# Quadcopter_v2.net
KiCad netlist of a schematic drawn in EAGLE
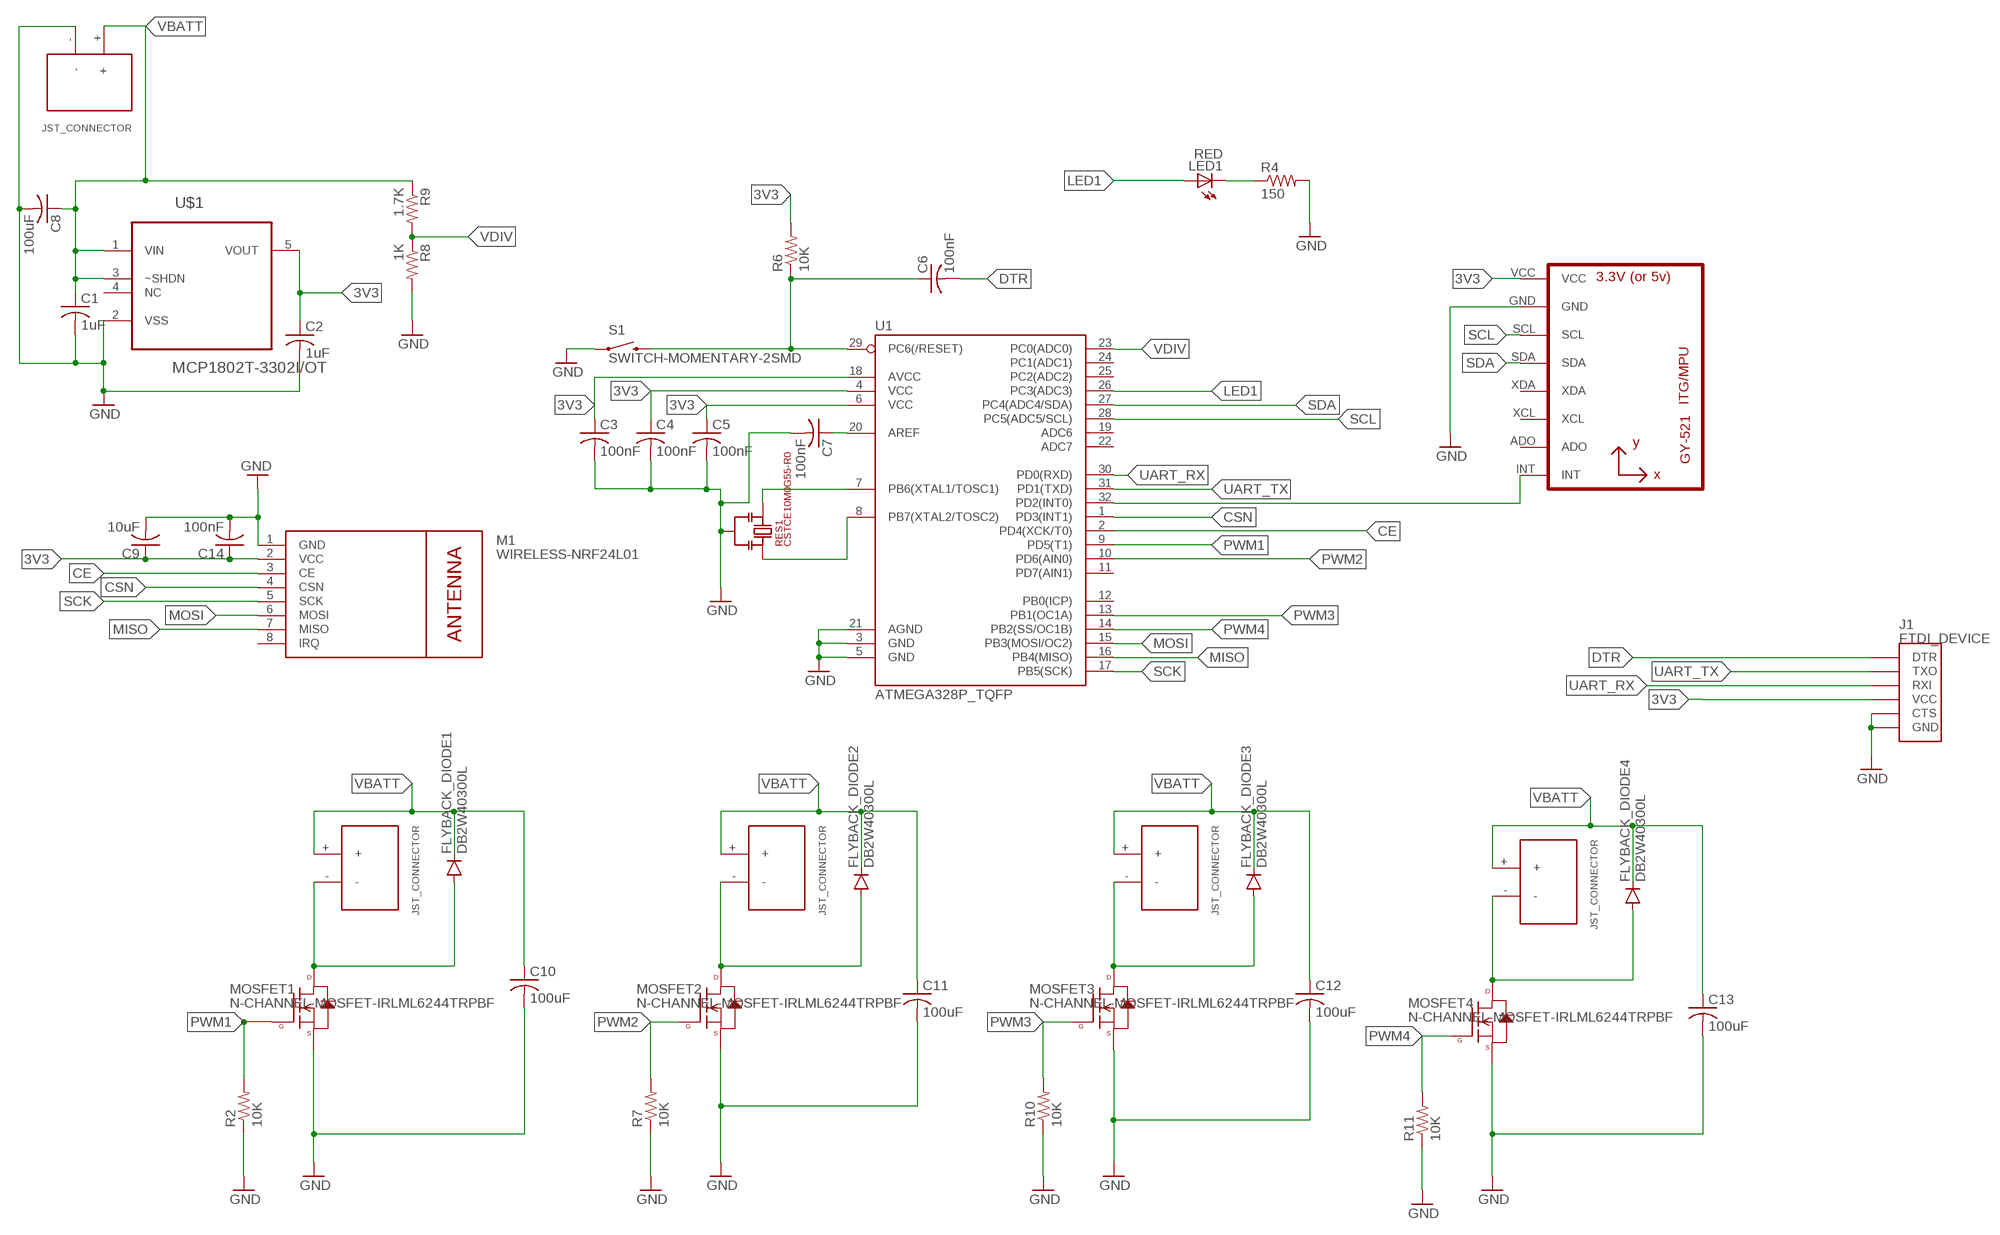
[diagram p0: schematic, sheet 1]

(export (version "E")
  (design (tool "Eeschema 10.0.6"))
  (components
    (comp (ref "C1")
      (value "1uF")
      (footprint "eagle-import:C0603")
      (libsource (lib "eagle-import") (part "C-USC0603"))
    )
    (comp (ref "C2")
      (value "1uF")
      (footprint "eagle-import:C0603")
      (libsource (lib "eagle-import") (part "C-USC0603"))
    )
    (comp (ref "C3")
      (value "100nF")
      (footprint "eagle-import:C0603")
      (libsource (lib "eagle-import") (part "C-USC0603"))
    )
    (comp (ref "C4")
      (value "100nF")
      (footprint "eagle-import:C0603")
      (libsource (lib "eagle-import") (part "C-USC0603"))
    )
    (comp (ref "C5")
      (value "100nF")
      (footprint "eagle-import:C0603")
      (libsource (lib "eagle-import") (part "C-USC0603"))
    )
    (comp (ref "C6")
      (value "100nF")
      (footprint "eagle-import:C0603")
      (libsource (lib "eagle-import") (part "C-USC0603"))
    )
    (comp (ref "C7")
      (value "100nF")
      (footprint "eagle-import:C0603")
      (libsource (lib "eagle-import") (part "C-USC0603"))
    )
    (comp (ref "C8")
      (value "100uF")
      (footprint "eagle-import:C1210")
      (libsource (lib "eagle-import") (part "C-USC1210"))
    )
    (comp (ref "C9")
      (value "10uF")
      (footprint "eagle-import:C0603")
      (libsource (lib "eagle-import") (part "C-USC0603"))
    )
    (comp (ref "C10")
      (value "100uF")
      (footprint "eagle-import:C1210")
      (libsource (lib "eagle-import") (part "C-USC1210"))
    )
    (comp (ref "C11")
      (value "100uF")
      (footprint "eagle-import:C1210")
      (libsource (lib "eagle-import") (part "C-USC1210"))
    )
    (comp (ref "C12")
      (value "100uF")
      (footprint "eagle-import:C1210")
      (libsource (lib "eagle-import") (part "C-USC1210"))
    )
    (comp (ref "C13")
      (value "100uF")
      (footprint "eagle-import:C1210")
      (libsource (lib "eagle-import") (part "C-USC1210"))
    )
    (comp (ref "C14")
      (value "100nF")
      (footprint "eagle-import:C0603")
      (libsource (lib "eagle-import") (part "C-USC0603"))
    )
    (comp (ref "FLYBACK_DIODE1")
      (value "DB2W40300L")
      (footprint "eagle-import:MINI2-F3-B")
      (libsource (lib "eagle-import") (part "DB2W40300L"))
    )
    (comp (ref "FLYBACK_DIODE2")
      (value "DB2W40300L")
      (footprint "eagle-import:MINI2-F3-B")
      (libsource (lib "eagle-import") (part "DB2W40300L"))
    )
    (comp (ref "FLYBACK_DIODE3")
      (value "DB2W40300L")
      (footprint "eagle-import:MINI2-F3-B")
      (libsource (lib "eagle-import") (part "DB2W40300L"))
    )
    (comp (ref "FLYBACK_DIODE4")
      (value "DB2W40300L")
      (footprint "eagle-import:MINI2-F3-B")
      (libsource (lib "eagle-import") (part "DB2W40300L"))
    )
    (comp (ref "J1")
      (value "FTDI_DEVICE")
      (footprint "eagle-import:FTDI_DEVICE_SIDE")
      (libsource (lib "eagle-import") (part "FTDI_DEVICE"))
    )
    (comp (ref "LED1")
      (value "RED")
      (footprint "eagle-import:CHIP-LED0603")
      (libsource (lib "eagle-import") (part "LEDCHIP-LED0603"))
    )
    (comp (ref "M1")
      (value "WIRELESS-NRF24L01")
      (footprint "eagle-import:WIRELESS-NRF24L01")
      (libsource (lib "eagle-import") (part "WIRELESS-NRF24L01"))
    )
    (comp (ref "MOSFET1")
      (value "N-CHANNEL-MOSFET-IRLML6244TRPBF")
      (footprint "eagle-import:SOT23-3")
      (libsource (lib "eagle-import") (part "N-CHANNEL-MOSFET-IRLML6244TRPBF"))
    )
    (comp (ref "MOSFET2")
      (value "N-CHANNEL-MOSFET-IRLML6244TRPBF")
      (footprint "eagle-import:SOT23-3")
      (libsource (lib "eagle-import") (part "N-CHANNEL-MOSFET-IRLML6244TRPBF"))
    )
    (comp (ref "MOSFET3")
      (value "N-CHANNEL-MOSFET-IRLML6244TRPBF")
      (footprint "eagle-import:SOT23-3")
      (libsource (lib "eagle-import") (part "N-CHANNEL-MOSFET-IRLML6244TRPBF"))
    )
    (comp (ref "MOSFET4")
      (value "N-CHANNEL-MOSFET-IRLML6244TRPBF")
      (footprint "eagle-import:SOT23-3")
      (libsource (lib "eagle-import") (part "N-CHANNEL-MOSFET-IRLML6244TRPBF"))
    )
    (comp (ref "MOTOR")
      (value "JST_CONNECTOR_FEMALE")
      (footprint "eagle-import:JST_CONNECTOR_FEMALE")
      (libsource (lib "eagle-import") (part "JST_CONNECTOR_FEMALE"))
    )
    (comp (ref "MOTOR1")
      (value "JST_CONNECTOR_FEMALE")
      (footprint "eagle-import:JST_CONNECTOR_FEMALE")
      (libsource (lib "eagle-import") (part "JST_CONNECTOR_FEMALE"))
    )
    (comp (ref "MOTOR2")
      (value "JST_CONNECTOR_FEMALE")
      (footprint "eagle-import:JST_CONNECTOR_FEMALE")
      (libsource (lib "eagle-import") (part "JST_CONNECTOR_FEMALE"))
    )
    (comp (ref "MOTOR3")
      (value "JST_CONNECTOR_FEMALE")
      (footprint "eagle-import:JST_CONNECTOR_FEMALE")
      (libsource (lib "eagle-import") (part "JST_CONNECTOR_FEMALE"))
    )
    (comp (ref "R2")
      (value "10K")
      (footprint "eagle-import:R0603")
      (libsource (lib "eagle-import") (part "R-US_R0603"))
    )
    (comp (ref "R4")
      (value "150")
      (footprint "eagle-import:R0603")
      (libsource (lib "eagle-import") (part "R-US_R0603"))
    )
    (comp (ref "R6")
      (value "10K")
      (footprint "eagle-import:R0603")
      (libsource (lib "eagle-import") (part "R-US_R0603"))
    )
    (comp (ref "R7")
      (value "10K")
      (footprint "eagle-import:R0603")
      (libsource (lib "eagle-import") (part "R-US_R0603"))
    )
    (comp (ref "R8")
      (value "1K")
      (footprint "eagle-import:R0603")
      (libsource (lib "eagle-import") (part "R-US_R0603"))
    )
    (comp (ref "R9")
      (value "1.7K")
      (footprint "eagle-import:R0603")
      (libsource (lib "eagle-import") (part "R-US_R0603"))
    )
    (comp (ref "R10")
      (value "10K")
      (footprint "eagle-import:R0603")
      (libsource (lib "eagle-import") (part "R-US_R0603"))
    )
    (comp (ref "R11")
      (value "10K")
      (footprint "eagle-import:R0603")
      (libsource (lib "eagle-import") (part "R-US_R0603"))
    )
    (comp (ref "RES1")
      (value "CSTCE10M0G55-R0")
      (footprint "eagle-import:CSTCE16M0V53-R0")
      (libsource (lib "eagle-import") (part "CSTCE-RESONATOR"))
    )
    (comp (ref "S1")
      (value "SWITCH-MOMENTARY-2SMD")
      (footprint "eagle-import:TACTILE-SWITCH-SMD")
      (libsource (lib "eagle-import") (part "SWITCH-MOMENTARY-2SMD"))
    )
    (comp (ref "U$1")
      (value "MCP1802T-3302I/OT")
      (footprint "eagle-import:SOT95P270X145-5N")
      (fields (field (name "MPN") "MCP1802T-3002I/OT"))
      (libsource (lib "eagle-import") (part "MCP1802T-3002I/OT"))
    )
    (comp (ref "U$2")
      (value "JST_Battery")
      (footprint "eagle-import:JST_CONNECTOR_FEMALE")
      (libsource (lib "eagle-import") (part "JST_CONNECTOR_FEMALE"))
    )
    (comp (ref "U1")
      (value "ATMEGA328P_TQFP")
      (footprint "eagle-import:TQFP32-08")
      (libsource (lib "eagle-import") (part "ATMEGA328P_TQFP"))
    )
    (comp (ref "U3")
      (value "GY-521MPU6050")
      (footprint "eagle-import:GY-521")
      (libsource (lib "eagle-import") (part "GY-521MPU6050"))
    )
  )
  (nets
    (net (code "1") (name "3V3") (class "Default")
      (node (ref "C14") (pin "1") (pinfunction "1_1") (pintype "passive"))
      (node (ref "C2") (pin "1") (pinfunction "1_1") (pintype "passive"))
      (node (ref "C3") (pin "1") (pinfunction "1_1") (pintype "passive"))
      (node (ref "C4") (pin "1") (pinfunction "1_1") (pintype "passive"))
      (node (ref "C5") (pin "1") (pinfunction "1_1") (pintype "passive"))
      (node (ref "C9") (pin "1") (pinfunction "1_1") (pintype "passive"))
      (node (ref "J1") (pin "P$4") (pinfunction "VCC_P$4") (pintype "bidirectional"))
      (node (ref "M1") (pin "2") (pinfunction "VCC_2") (pintype "power_in"))
      (node (ref "R6") (pin "2") (pinfunction "2_2") (pintype "passive"))
      (node (ref "U$1") (pin "5") (pinfunction "VOUT_5") (pintype "output"))
      (node (ref "U1") (pin "18") (pinfunction "AVCC_18") (pintype "bidirectional"))
      (node (ref "U1") (pin "4") (pinfunction "VCC_4") (pintype "bidirectional"))
      (node (ref "U1") (pin "6") (pinfunction "VCC_6") (pintype "bidirectional"))
      (node (ref "U3") (pin "VCC") (pinfunction "VCC_VCC") (pintype "bidirectional"))
    )
    (net (code "2") (name "CE") (class "Default")
      (node (ref "M1") (pin "3") (pinfunction "CE_3") (pintype "bidirectional"))
      (node (ref "U1") (pin "2") (pinfunction "PD4(XCK/T0)_2") (pintype "bidirectional"))
    )
    (net (code "3") (name "CSN") (class "Default")
      (node (ref "M1") (pin "4") (pinfunction "CSN_4") (pintype "bidirectional"))
      (node (ref "U1") (pin "1") (pinfunction "PD3(INT1)_1") (pintype "bidirectional"))
    )
    (net (code "4") (name "DTR") (class "Default")
      (node (ref "C6") (pin "2") (pinfunction "2_2") (pintype "passive"))
      (node (ref "J1") (pin "P$1") (pinfunction "DTR_P$1") (pintype "bidirectional"))
    )
    (net (code "5") (name "GND") (class "Default")
      (node (ref "C1") (pin "2") (pinfunction "2_2") (pintype "passive"))
      (node (ref "C10") (pin "2") (pinfunction "2_2") (pintype "passive"))
      (node (ref "C11") (pin "2") (pinfunction "2_2") (pintype "passive"))
      (node (ref "C12") (pin "2") (pinfunction "2_2") (pintype "passive"))
      (node (ref "C13") (pin "2") (pinfunction "2_2") (pintype "passive"))
      (node (ref "C14") (pin "2") (pinfunction "2_2") (pintype "passive"))
      (node (ref "C2") (pin "2") (pinfunction "2_2") (pintype "passive"))
      (node (ref "C3") (pin "2") (pinfunction "2_2") (pintype "passive"))
      (node (ref "C4") (pin "2") (pinfunction "2_2") (pintype "passive"))
      (node (ref "C5") (pin "2") (pinfunction "2_2") (pintype "passive"))
      (node (ref "C7") (pin "2") (pinfunction "2_2") (pintype "passive"))
      (node (ref "C8") (pin "2") (pinfunction "2_2") (pintype "passive"))
      (node (ref "C9") (pin "2") (pinfunction "2_2") (pintype "passive"))
      (node (ref "J1") (pin "P$5") (pinfunction "CTS_P$5") (pintype "bidirectional"))
      (node (ref "J1") (pin "P$6") (pinfunction "GND_P$6") (pintype "bidirectional"))
      (node (ref "M1") (pin "1") (pinfunction "GND_1") (pintype "power_in"))
      (node (ref "MOSFET1") (pin "2") (pinfunction "S_2") (pintype "passive"))
      (node (ref "MOSFET2") (pin "2") (pinfunction "S_2") (pintype "passive"))
      (node (ref "MOSFET3") (pin "2") (pinfunction "S_2") (pintype "passive"))
      (node (ref "MOSFET4") (pin "2") (pinfunction "S_2") (pintype "passive"))
      (node (ref "R10") (pin "1") (pinfunction "1_1") (pintype "passive"))
      (node (ref "R11") (pin "1") (pinfunction "1_1") (pintype "passive"))
      (node (ref "R2") (pin "1") (pinfunction "1_1") (pintype "passive"))
      (node (ref "R4") (pin "2") (pinfunction "2_2") (pintype "passive"))
      (node (ref "R7") (pin "1") (pinfunction "1_1") (pintype "passive"))
      (node (ref "R8") (pin "2") (pinfunction "2_2") (pintype "passive"))
      (node (ref "RES1") (pin "P$2") (pinfunction "P$2_P$2") (pintype "bidirectional"))
      (node (ref "S1") (pin "1") (pinfunction "1_1") (pintype "passive"))
      (node (ref "U$1") (pin "2") (pinfunction "VSS_2") (pintype "passive"))
      (node (ref "U$2") (pin "-") (pinfunction "-_-") (pintype "bidirectional"))
      (node (ref "U1") (pin "21") (pinfunction "AGND_21") (pintype "bidirectional"))
      (node (ref "U1") (pin "3") (pinfunction "GND_3") (pintype "bidirectional"))
      (node (ref "U1") (pin "5") (pinfunction "GND_5") (pintype "bidirectional"))
      (node (ref "U3") (pin "GND") (pinfunction "GND_GND") (pintype "bidirectional"))
    )
    (net (code "6") (name "LED1") (class "Default")
      (node (ref "LED1") (pin "A") (pinfunction "A_A") (pintype "passive"))
      (node (ref "U1") (pin "26") (pinfunction "PC3(ADC3)_26") (pintype "bidirectional"))
    )
    (net (code "7") (name "MISO") (class "Default")
      (node (ref "M1") (pin "7") (pinfunction "MISO_7") (pintype "bidirectional"))
      (node (ref "U1") (pin "16") (pinfunction "PB4(MISO)_16") (pintype "bidirectional"))
    )
    (net (code "8") (name "MOSI") (class "Default")
      (node (ref "M1") (pin "6") (pinfunction "MOSI_6") (pintype "bidirectional"))
      (node (ref "U1") (pin "15") (pinfunction "PB3(MOSI/OC2)_15") (pintype "bidirectional"))
    )
    (net (code "9") (name "Net-(FLYBACK_DIODE1-PPIN)") (class "Default")
      (node (ref "FLYBACK_DIODE1") (pin "POS") (pinfunction "PPIN_POS") (pintype "passive"))
      (node (ref "MOSFET1") (pin "3") (pinfunction "D_3") (pintype "passive"))
      (node (ref "MOTOR") (pin "-") (pinfunction "-_-") (pintype "bidirectional"))
    )
    (net (code "10") (name "Net-(FLYBACK_DIODE2-PPIN)") (class "Default")
      (node (ref "FLYBACK_DIODE2") (pin "POS") (pinfunction "PPIN_POS") (pintype "passive"))
      (node (ref "MOSFET2") (pin "3") (pinfunction "D_3") (pintype "passive"))
      (node (ref "MOTOR1") (pin "-") (pinfunction "-_-") (pintype "bidirectional"))
    )
    (net (code "11") (name "Net-(FLYBACK_DIODE3-PPIN)") (class "Default")
      (node (ref "FLYBACK_DIODE3") (pin "POS") (pinfunction "PPIN_POS") (pintype "passive"))
      (node (ref "MOSFET3") (pin "3") (pinfunction "D_3") (pintype "passive"))
      (node (ref "MOTOR2") (pin "-") (pinfunction "-_-") (pintype "bidirectional"))
    )
    (net (code "12") (name "Net-(FLYBACK_DIODE4-PPIN)") (class "Default")
      (node (ref "FLYBACK_DIODE4") (pin "POS") (pinfunction "PPIN_POS") (pintype "passive"))
      (node (ref "MOSFET4") (pin "3") (pinfunction "D_3") (pintype "passive"))
      (node (ref "MOTOR3") (pin "-") (pinfunction "-_-") (pintype "bidirectional"))
    )
    (net (code "13") (name "Net-(LED1-PadC)") (class "Default")
      (node (ref "LED1") (pin "C") (pinfunction "C_C") (pintype "passive"))
      (node (ref "R4") (pin "1") (pinfunction "1_1") (pintype "passive"))
    )
    (net (code "14") (name "Net-(S1-2)") (class "Default")
      (node (ref "C6") (pin "1") (pinfunction "1_1") (pintype "passive"))
      (node (ref "R6") (pin "1") (pinfunction "1_1") (pintype "passive"))
      (node (ref "S1") (pin "3") (pinfunction "2_3") (pintype "passive"))
      (node (ref "U1") (pin "29") (pinfunction "PC6(/RESET)_29") (pintype "bidirectional"))
    )
    (net (code "15") (name "Net-(U1-AREF)") (class "Default")
      (node (ref "C7") (pin "1") (pinfunction "1_1") (pintype "passive"))
      (node (ref "U1") (pin "20") (pinfunction "AREF_20") (pintype "bidirectional"))
    )
    (net (code "16") (name "Net-(U1-PB6(XTAL1{slash}TOSC1))") (class "Default")
      (node (ref "RES1") (pin "P$3") (pinfunction "P$3_P$3") (pintype "bidirectional"))
      (node (ref "U1") (pin "7") (pinfunction "PB6(XTAL1/TOSC1)_7") (pintype "bidirectional"))
    )
    (net (code "17") (name "Net-(U1-PB7(XTAL2{slash}TOSC2))") (class "Default")
      (node (ref "RES1") (pin "P$1") (pinfunction "P$1_P$1") (pintype "bidirectional"))
      (node (ref "U1") (pin "8") (pinfunction "PB7(XTAL2/TOSC2)_8") (pintype "bidirectional"))
    )
    (net (code "18") (name "Net-(U1-PD2(INT0))") (class "Default")
      (node (ref "U1") (pin "32") (pinfunction "PD2(INT0)_32") (pintype "bidirectional"))
      (node (ref "U3") (pin "INT") (pinfunction "INT_INT") (pintype "bidirectional"))
    )
    (net (code "19") (name "PWM1") (class "Default")
      (node (ref "MOSFET1") (pin "1") (pinfunction "G_1") (pintype "passive"))
      (node (ref "R2") (pin "2") (pinfunction "2_2") (pintype "passive"))
      (node (ref "U1") (pin "9") (pinfunction "PD5(T1)_9") (pintype "bidirectional"))
    )
    (net (code "20") (name "PWM2") (class "Default")
      (node (ref "MOSFET2") (pin "1") (pinfunction "G_1") (pintype "passive"))
      (node (ref "R7") (pin "2") (pinfunction "2_2") (pintype "passive"))
      (node (ref "U1") (pin "10") (pinfunction "PD6(AIN0)_10") (pintype "bidirectional"))
    )
    (net (code "21") (name "PWM3") (class "Default")
      (node (ref "MOSFET3") (pin "1") (pinfunction "G_1") (pintype "passive"))
      (node (ref "R10") (pin "2") (pinfunction "2_2") (pintype "passive"))
      (node (ref "U1") (pin "13") (pinfunction "PB1(OC1A)_13") (pintype "bidirectional"))
    )
    (net (code "22") (name "PWM4") (class "Default")
      (node (ref "MOSFET4") (pin "1") (pinfunction "G_1") (pintype "passive"))
      (node (ref "R11") (pin "2") (pinfunction "2_2") (pintype "passive"))
      (node (ref "U1") (pin "14") (pinfunction "PB2(SS/OC1B)_14") (pintype "bidirectional"))
    )
    (net (code "23") (name "SCK") (class "Default")
      (node (ref "M1") (pin "5") (pinfunction "SCK_5") (pintype "bidirectional"))
      (node (ref "U1") (pin "17") (pinfunction "PB5(SCK)_17") (pintype "bidirectional"))
    )
    (net (code "24") (name "SCL") (class "Default")
      (node (ref "U1") (pin "28") (pinfunction "PC5(ADC5/SCL)_28") (pintype "bidirectional"))
      (node (ref "U3") (pin "SCL") (pinfunction "SCL_SCL") (pintype "bidirectional"))
    )
    (net (code "25") (name "SDA") (class "Default")
      (node (ref "U1") (pin "27") (pinfunction "PC4(ADC4/SDA)_27") (pintype "bidirectional"))
      (node (ref "U3") (pin "SDA") (pinfunction "SDA_SDA") (pintype "bidirectional"))
    )
    (net (code "26") (name "UART_RX") (class "Default")
      (node (ref "J1") (pin "P$3") (pinfunction "RXI_P$3") (pintype "bidirectional"))
      (node (ref "U1") (pin "30") (pinfunction "PD0(RXD)_30") (pintype "bidirectional"))
    )
    (net (code "27") (name "UART_TX") (class "Default")
      (node (ref "J1") (pin "P$2") (pinfunction "TXO_P$2") (pintype "bidirectional"))
      (node (ref "U1") (pin "31") (pinfunction "PD1(TXD)_31") (pintype "bidirectional"))
    )
    (net (code "28") (name "VBATT") (class "Default")
      (node (ref "C1") (pin "1") (pinfunction "1_1") (pintype "passive"))
      (node (ref "C10") (pin "1") (pinfunction "1_1") (pintype "passive"))
      (node (ref "C11") (pin "1") (pinfunction "1_1") (pintype "passive"))
      (node (ref "C12") (pin "1") (pinfunction "1_1") (pintype "passive"))
      (node (ref "C13") (pin "1") (pinfunction "1_1") (pintype "passive"))
      (node (ref "C8") (pin "1") (pinfunction "1_1") (pintype "passive"))
      (node (ref "FLYBACK_DIODE1") (pin "NEG") (pinfunction "GPIN_NEG") (pintype "passive"))
      (node (ref "FLYBACK_DIODE2") (pin "NEG") (pinfunction "GPIN_NEG") (pintype "passive"))
      (node (ref "FLYBACK_DIODE3") (pin "NEG") (pinfunction "GPIN_NEG") (pintype "passive"))
      (node (ref "FLYBACK_DIODE4") (pin "NEG") (pinfunction "GPIN_NEG") (pintype "passive"))
      (node (ref "MOTOR") (pin "+") (pinfunction "+_+") (pintype "bidirectional"))
      (node (ref "MOTOR1") (pin "+") (pinfunction "+_+") (pintype "bidirectional"))
      (node (ref "MOTOR2") (pin "+") (pinfunction "+_+") (pintype "bidirectional"))
      (node (ref "MOTOR3") (pin "+") (pinfunction "+_+") (pintype "bidirectional"))
      (node (ref "R9") (pin "1") (pinfunction "1_1") (pintype "passive"))
      (node (ref "U$1") (pin "1") (pinfunction "VIN_1") (pintype "power_in"))
      (node (ref "U$1") (pin "3") (pinfunction "~{SHDN}_3") (pintype "input"))
      (node (ref "U$2") (pin "+") (pinfunction "+_+") (pintype "bidirectional"))
    )
    (net (code "29") (name "VDIV") (class "Default")
      (node (ref "R8") (pin "1") (pinfunction "1_1") (pintype "passive"))
      (node (ref "R9") (pin "2") (pinfunction "2_2") (pintype "passive"))
      (node (ref "U1") (pin "23") (pinfunction "PC0(ADC0)_23") (pintype "bidirectional"))
    )
    (net (code "30") (name "unconnected-(M1-IRQ-Pad8)") (class "Default")
      (node (ref "M1") (pin "8") (pinfunction "IRQ_8") (pintype "bidirectional"))
    )
    (net (code "31") (name "unconnected-(U$1-NC-Pad4)") (class "Default")
      (node (ref "U$1") (pin "4") (pinfunction "NC_4") (pintype "no_connect"))
    )
    (net (code "32") (name "unconnected-(U1-ADC6-Pad19)") (class "Default")
      (node (ref "U1") (pin "19") (pinfunction "ADC6_19") (pintype "bidirectional"))
    )
    (net (code "33") (name "unconnected-(U1-ADC7-Pad22)") (class "Default")
      (node (ref "U1") (pin "22") (pinfunction "ADC7_22") (pintype "bidirectional"))
    )
    (net (code "34") (name "unconnected-(U1-PB0(ICP)-Pad12)") (class "Default")
      (node (ref "U1") (pin "12") (pinfunction "PB0(ICP)_12") (pintype "bidirectional"))
    )
    (net (code "35") (name "unconnected-(U1-PC1(ADC1)-Pad24)") (class "Default")
      (node (ref "U1") (pin "24") (pinfunction "PC1(ADC1)_24") (pintype "bidirectional"))
    )
    (net (code "36") (name "unconnected-(U1-PC2(ADC2)-Pad25)") (class "Default")
      (node (ref "U1") (pin "25") (pinfunction "PC2(ADC2)_25") (pintype "bidirectional"))
    )
    (net (code "37") (name "unconnected-(U1-PD7(AIN1)-Pad11)") (class "Default")
      (node (ref "U1") (pin "11") (pinfunction "PD7(AIN1)_11") (pintype "bidirectional"))
    )
    (net (code "38") (name "unconnected-(U3-PadADO)") (class "Default")
      (node (ref "U3") (pin "ADO") (pinfunction "ADO_ADO") (pintype "bidirectional"))
    )
    (net (code "39") (name "unconnected-(U3-PadXCL)") (class "Default")
      (node (ref "U3") (pin "XCL") (pinfunction "XCL_XCL") (pintype "bidirectional"))
    )
    (net (code "40") (name "unconnected-(U3-PadXDA)") (class "Default")
      (node (ref "U3") (pin "XDA") (pinfunction "XDA_XDA") (pintype "bidirectional"))
    )
  )
)
